# MCU.net
KiCad netlist of a schematic drawn in Altium Designer
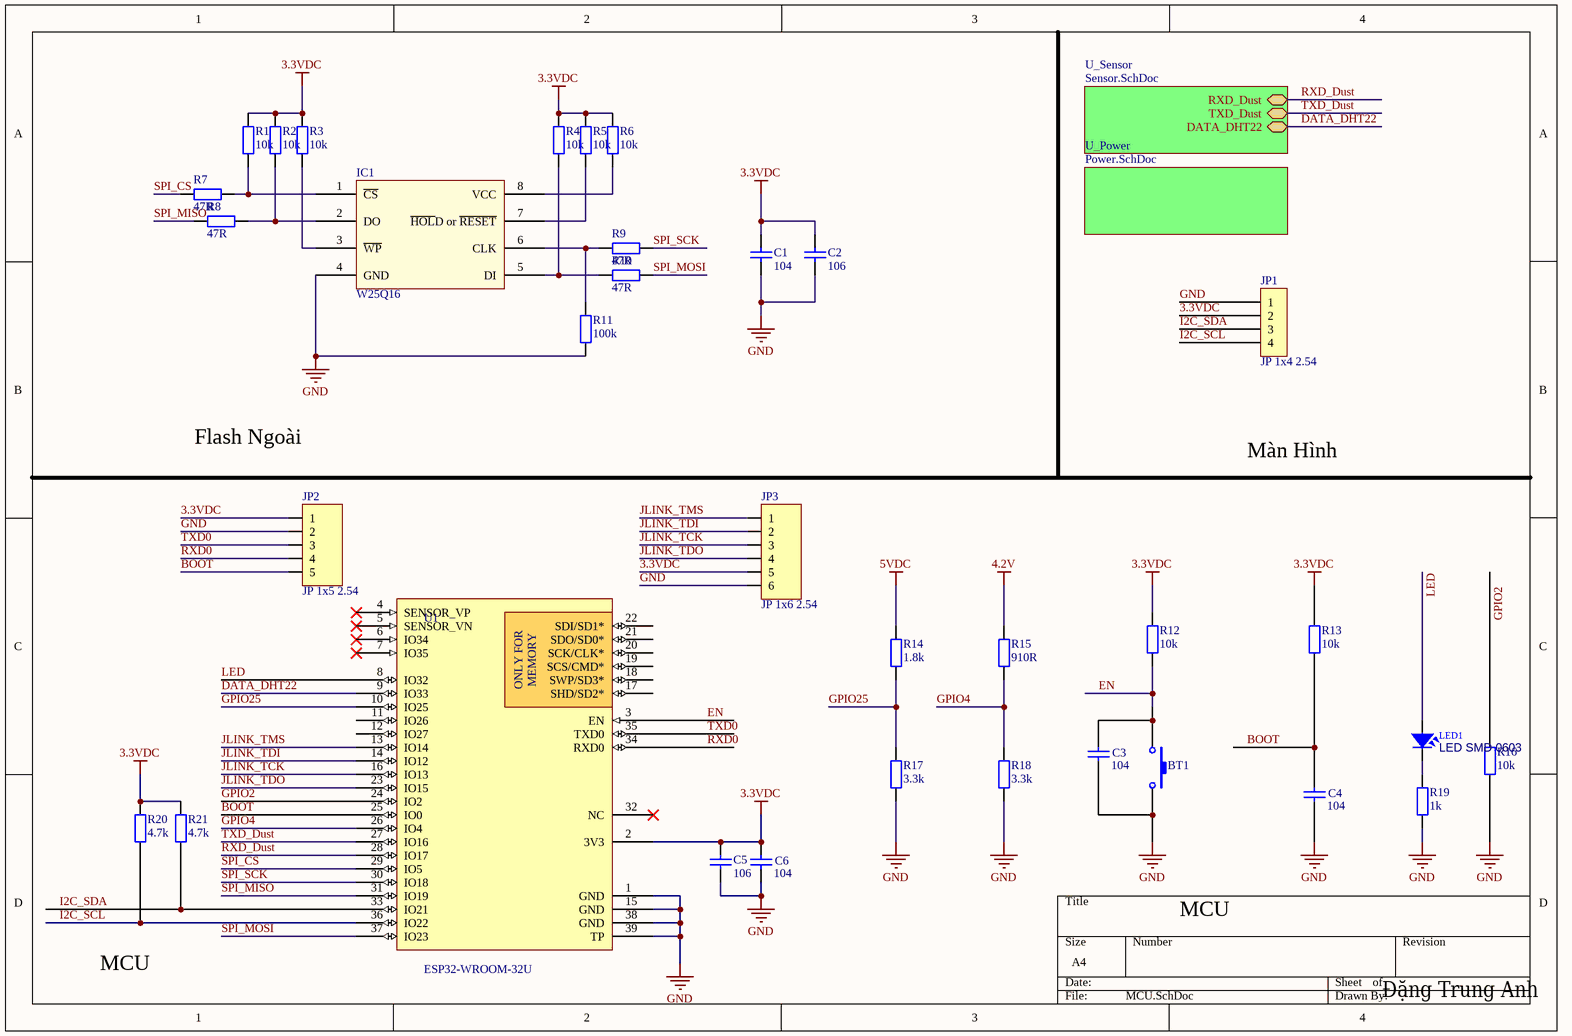
[diagram p0: MCU.SchDoc]

(export (version "E")
  (design (tool "Eeschema 10.0.6"))
  (components
    (comp (ref "BT1")
      (value "Nut Nhan 2 Chan SMD 3x6x2.5")
      (footprint "Nut Nhan 2 Chan SMD 3x6x2.5")
      (libsource (lib "Altium_Lib_by_KhueNguyenCreator") (part "Nut Nhan 2 Chan SMD 3x6x2.5"))
    )
    (comp (ref "C1")
      (value "104")
      (footprint "tu 0603")
      (description "Dán")
      (libsource (lib "Altium_Lib_by_KhueNguyenCreator") (part "Tu 0603 104 50V 10%"))
    )
    (comp (ref "C2")
      (value "106")
      (footprint "tu 0603")
      (description "Dán")
      (libsource (lib "THU VIEN SCH") (part "Tu 0603 106 16V 20%"))
    )
    (comp (ref "C3")
      (value "104")
      (footprint "tu 0603")
      (description "Dán")
      (libsource (lib "Altium_Lib_by_KhueNguyenCreator") (part "Tu 0603 104 50V 10%"))
    )
    (comp (ref "C4")
      (value "104")
      (footprint "tu 0603")
      (description "Dán")
      (libsource (lib "Altium_Lib_by_KhueNguyenCreator") (part "Tu 0603 104 50V 10%"))
    )
    (comp (ref "C5")
      (value "106")
      (footprint "tu 0603")
      (description "Dán")
      (libsource (lib "THU VIEN SCH") (part "Tu 0603 106 16V 20%"))
    )
    (comp (ref "C6")
      (value "104")
      (footprint "tu 0603")
      (description "Dán")
      (libsource (lib "Altium_Lib_by_KhueNguyenCreator") (part "Tu 0603 104 50V 10%"))
    )
    (comp (ref "IC1")
      (value "W25Q16")
      (footprint "W25Q16 -SOIC8")
      (libsource (lib "Integrated_Library") (part "W25Q16"))
    )
    (comp (ref "JP1")
      (value "JP 1x4 2.54")
      (footprint "JP 1x4 DT")
      (description "Cắm")
      (libsource (lib "Altium_Lib_by_KhueNguyenCreator") (part "JP 1x4 2.54 Duc Thang"))
    )
    (comp (ref "JP2")
      (value "JP 1x5 2.54")
      (footprint "JP 1x5 DT")
      (description "Cắm")
      (libsource (lib "Altium_Lib_by_KhueNguyenCreator") (part "JP 1x5 2.54 Duc Thang"))
    )
    (comp (ref "JP3")
      (value "JP 1x6 2.54")
      (footprint "JP 1x6 DT")
      (description "Cắm")
      (libsource (lib "Altium_Lib_by_KhueNguyenCreator") (part "JP 1x6 2.54 Duc Thang"))
    )
    (comp (ref "LED1")
      (value "LED SMD 0603")
      (footprint "LED-0603-BLUE")
      (description "LED 0603 SMD Green 525nm 350mcd 20mA")
      (libsource (lib "My library altium") (part "LED SMD 0603"))
    )
    (comp (ref "R1")
      (value "10k")
      (footprint "tro smd 0603")
      (description "Dán")
      (libsource (lib "THU VIEN SCH") (part "Tro 0603 1% 10k"))
    )
    (comp (ref "R2")
      (value "10k")
      (footprint "tro smd 0603")
      (description "Dán")
      (libsource (lib "THU VIEN SCH") (part "Tro 0603 1% 10k"))
    )
    (comp (ref "R3")
      (value "10k")
      (footprint "tro smd 0603")
      (description "Dán")
      (libsource (lib "THU VIEN SCH") (part "Tro 0603 1% 10k"))
    )
    (comp (ref "R4")
      (value "10k")
      (footprint "tro smd 0603")
      (description "Dán")
      (libsource (lib "THU VIEN SCH") (part "Tro 0603 1% 10k"))
    )
    (comp (ref "R5")
      (value "10k")
      (footprint "tro smd 0603")
      (description "Dán")
      (libsource (lib "THU VIEN SCH") (part "Tro 0603 1% 10k"))
    )
    (comp (ref "R6")
      (value "10k")
      (footprint "tro smd 0603")
      (description "Dán")
      (libsource (lib "THU VIEN SCH") (part "Tro 0603 1% 10k"))
    )
    (comp (ref "R7")
      (value "47R")
      (footprint "tro smd 0603")
      (description "Dán")
      (libsource (lib "Altium_Lib_by_KhueNguyenCreator") (part "Tro 0603 1% 47R"))
    )
    (comp (ref "R8")
      (value "47R")
      (footprint "tro smd 0603")
      (description "Dán")
      (libsource (lib "Altium_Lib_by_KhueNguyenCreator") (part "Tro 0603 1% 47R"))
    )
    (comp (ref "R9")
      (value "47R")
      (footprint "tro smd 0603")
      (description "Dán")
      (libsource (lib "Altium_Lib_by_KhueNguyenCreator") (part "Tro 0603 1% 47R"))
    )
    (comp (ref "R10")
      (value "47R")
      (footprint "tro smd 0603")
      (description "Dán")
      (libsource (lib "Altium_Lib_by_KhueNguyenCreator") (part "Tro 0603 1% 47R"))
    )
    (comp (ref "R11")
      (value "100k")
      (footprint "tro smd 0603")
      (description "Dán")
      (libsource (lib "Altium_Lib_by_KhueNguyenCreator") (part "Tro 0603 5% 100k"))
    )
    (comp (ref "R12")
      (value "10k")
      (footprint "tro smd 0603")
      (description "Dán")
      (libsource (lib "THU VIEN SCH") (part "Tro 0603 1% 10k"))
    )
    (comp (ref "R13")
      (value "10k")
      (footprint "tro smd 0603")
      (description "Dán")
      (libsource (lib "THU VIEN SCH") (part "Tro 0603 1% 10k"))
    )
    (comp (ref "R14")
      (value "1.8k")
      (footprint "tro smd 0603")
      (description "Dán")
      (libsource (lib "Altium_Lib_by_KhueNguyenCreator") (part "Tro 0603 1% 1.8k"))
    )
    (comp (ref "R15")
      (value "910R")
      (footprint "tro smd 0603")
      (description "Dán")
      (libsource (lib "Altium_Lib_by_KhueNguyenCreator") (part "Tro 0603 1% 910R"))
    )
    (comp (ref "R16")
      (value "10k")
      (footprint "tro smd 0603")
      (description "Dán")
      (libsource (lib "THU VIEN SCH") (part "Tro 0603 1% 10k"))
    )
    (comp (ref "R17")
      (value "3.3k")
      (footprint "tro smd 0603")
      (description "Dán")
      (libsource (lib "Altium_Lib_by_KhueNguyenCreator") (part "Tro 0603 5% 3.3k"))
    )
    (comp (ref "R18")
      (value "3.3k")
      (footprint "tro smd 0603")
      (description "Dán")
      (libsource (lib "Altium_Lib_by_KhueNguyenCreator") (part "Tro 0603 5% 3.3k"))
    )
    (comp (ref "R19")
      (value "1k")
      (footprint "tro smd 0603")
      (description "Dán")
      (libsource (lib "Altium_Lib_by_KhueNguyenCreator") (part "Tro 0603 5% 1k"))
    )
    (comp (ref "R20")
      (value "4.7k")
      (footprint "tro smd 0603")
      (description "Dán")
      (libsource (lib "Altium_Lib_by_KhueNguyenCreator") (part "Tro 0603 5% 4.7k"))
    )
    (comp (ref "R21")
      (value "4.7k")
      (footprint "tro smd 0603")
      (description "Dán")
      (libsource (lib "Altium_Lib_by_KhueNguyenCreator") (part "Tro 0603 5% 4.7k"))
    )
    (comp (ref "U1")
      (value "ESP32-WROOM-32U")
      (footprint "ESP32-WROOM-32")
      (description "Wi-Fi/BT BLE Module ESP32-D0WD")
      (fields (field (name "MFR") "Espressif"))
      (libsource (lib "BYTECH_HW_LIB_2019 (1)") (part "ESP32-WROOM-32U"))
    )
  )
  (nets
    (net (code "1") (name "/BOOT") (class "Default")
      (node (ref "C4") (pin "1") (pinfunction "1_1") (pintype "passive"))
      (node (ref "JP2") (pin "5") (pinfunction "5_5") (pintype "passive"))
      (node (ref "R13") (pin "1") (pinfunction "1_1") (pintype "passive"))
      (node (ref "U1") (pin "25") (pinfunction "IO0_25") (pintype "bidirectional"))
    )
    (net (code "2") (name "/DATA_DHT22") (class "Default")
      (node (ref "U1") (pin "9") (pinfunction "IO33_9") (pintype "bidirectional"))
    )
    (net (code "3") (name "/EN") (class "Default")
      (node (ref "BT1") (pin "1") (pinfunction "1_1") (pintype "passive"))
      (node (ref "C3") (pin "1") (pinfunction "1_1") (pintype "passive"))
      (node (ref "R12") (pin "1") (pinfunction "1_1") (pintype "passive"))
      (node (ref "U1") (pin "3") (pinfunction "EN_3") (pintype "input"))
    )
    (net (code "4") (name "/GPIO2") (class "Default")
      (node (ref "R16") (pin "2") (pinfunction "2_2") (pintype "passive"))
      (node (ref "U1") (pin "24") (pinfunction "IO2_24") (pintype "bidirectional"))
    )
    (net (code "5") (name "/GPIO4") (class "Default")
      (node (ref "R15") (pin "1") (pinfunction "1_1") (pintype "passive"))
      (node (ref "R18") (pin "2") (pinfunction "2_2") (pintype "passive"))
      (node (ref "U1") (pin "26") (pinfunction "IO4_26") (pintype "bidirectional"))
    )
    (net (code "6") (name "/GPIO25") (class "Default")
      (node (ref "R14") (pin "1") (pinfunction "1_1") (pintype "passive"))
      (node (ref "R17") (pin "2") (pinfunction "2_2") (pintype "passive"))
      (node (ref "U1") (pin "10") (pinfunction "IO25_10") (pintype "bidirectional"))
    )
    (net (code "7") (name "/I2C_SCL") (class "Default")
      (node (ref "JP1") (pin "4") (pinfunction "4_4") (pintype "passive"))
      (node (ref "R20") (pin "1") (pinfunction "1_1") (pintype "passive"))
      (node (ref "U1") (pin "36") (pinfunction "IO22_36") (pintype "bidirectional"))
    )
    (net (code "8") (name "/I2C_SDA") (class "Default")
      (node (ref "JP1") (pin "3") (pinfunction "3_3") (pintype "passive"))
      (node (ref "R21") (pin "1") (pinfunction "1_1") (pintype "passive"))
      (node (ref "U1") (pin "33") (pinfunction "IO21_33") (pintype "bidirectional"))
    )
    (net (code "9") (name "/JLINK_TCK") (class "Default")
      (node (ref "JP3") (pin "3") (pinfunction "3_3") (pintype "passive"))
      (node (ref "U1") (pin "16") (pinfunction "IO13_16") (pintype "bidirectional"))
    )
    (net (code "10") (name "/JLINK_TDI") (class "Default")
      (node (ref "JP3") (pin "2") (pinfunction "2_2") (pintype "passive"))
      (node (ref "U1") (pin "14") (pinfunction "IO12_14") (pintype "bidirectional"))
    )
    (net (code "11") (name "/JLINK_TDO") (class "Default")
      (node (ref "JP3") (pin "4") (pinfunction "4_4") (pintype "passive"))
      (node (ref "U1") (pin "23") (pinfunction "IO15_23") (pintype "bidirectional"))
    )
    (net (code "12") (name "/JLINK_TMS") (class "Default")
      (node (ref "JP3") (pin "1") (pinfunction "1_1") (pintype "passive"))
      (node (ref "U1") (pin "13") (pinfunction "IO14_13") (pintype "bidirectional"))
    )
    (net (code "13") (name "/LED") (class "Default")
      (node (ref "LED1") (pin "A") (pinfunction "A_A") (pintype "passive"))
      (node (ref "U1") (pin "8") (pinfunction "IO32_8") (pintype "bidirectional"))
    )
    (net (code "14") (name "/RXD0") (class "Default")
      (node (ref "JP2") (pin "4") (pinfunction "4_4") (pintype "passive"))
      (node (ref "U1") (pin "34") (pinfunction "RXD0_34") (pintype "bidirectional"))
    )
    (net (code "15") (name "/RXD_Dust") (class "Default")
      (node (ref "U1") (pin "28") (pinfunction "IO17_28") (pintype "bidirectional"))
    )
    (net (code "16") (name "/SPI_CS") (class "Default")
      (node (ref "R7") (pin "1") (pinfunction "1_1") (pintype "passive"))
      (node (ref "U1") (pin "29") (pinfunction "IO5_29") (pintype "bidirectional"))
    )
    (net (code "17") (name "/SPI_MISO") (class "Default")
      (node (ref "R8") (pin "1") (pinfunction "1_1") (pintype "passive"))
      (node (ref "U1") (pin "31") (pinfunction "IO19_31") (pintype "bidirectional"))
    )
    (net (code "18") (name "/SPI_MOSI") (class "Default")
      (node (ref "R10") (pin "2") (pinfunction "2_2") (pintype "passive"))
      (node (ref "U1") (pin "37") (pinfunction "IO23_37") (pintype "bidirectional"))
    )
    (net (code "19") (name "/SPI_SCK") (class "Default")
      (node (ref "R9") (pin "2") (pinfunction "2_2") (pintype "passive"))
      (node (ref "U1") (pin "30") (pinfunction "IO18_30") (pintype "bidirectional"))
    )
    (net (code "20") (name "/TXD0") (class "Default")
      (node (ref "JP2") (pin "3") (pinfunction "3_3") (pintype "passive"))
      (node (ref "U1") (pin "35") (pinfunction "TXD0_35") (pintype "bidirectional"))
    )
    (net (code "21") (name "/TXD_Dust") (class "Default")
      (node (ref "U1") (pin "27") (pinfunction "IO16_27") (pintype "bidirectional"))
    )
    (net (code "22") (name "3.3VDC") (class "Default")
      (node (ref "C1") (pin "1") (pinfunction "1_1") (pintype "passive"))
      (node (ref "C2") (pin "1") (pinfunction "1_1") (pintype "passive"))
      (node (ref "C5") (pin "1") (pinfunction "1_1") (pintype "passive"))
      (node (ref "C6") (pin "1") (pinfunction "1_1") (pintype "passive"))
      (node (ref "JP1") (pin "2") (pinfunction "2_2") (pintype "passive"))
      (node (ref "JP2") (pin "1") (pinfunction "1_1") (pintype "passive"))
      (node (ref "JP3") (pin "5") (pinfunction "5_5") (pintype "passive"))
      (node (ref "R1") (pin "2") (pinfunction "2_2") (pintype "passive"))
      (node (ref "R12") (pin "2") (pinfunction "2_2") (pintype "passive"))
      (node (ref "R13") (pin "2") (pinfunction "2_2") (pintype "passive"))
      (node (ref "R2") (pin "2") (pinfunction "2_2") (pintype "passive"))
      (node (ref "R20") (pin "2") (pinfunction "2_2") (pintype "passive"))
      (node (ref "R21") (pin "2") (pinfunction "2_2") (pintype "passive"))
      (node (ref "R3") (pin "2") (pinfunction "2_2") (pintype "passive"))
      (node (ref "R4") (pin "2") (pinfunction "2_2") (pintype "passive"))
      (node (ref "R5") (pin "2") (pinfunction "2_2") (pintype "passive"))
      (node (ref "R6") (pin "2") (pinfunction "2_2") (pintype "passive"))
      (node (ref "U1") (pin "2") (pinfunction "3V3_2") (pintype "power_in"))
    )
    (net (code "23") (name "4.2V") (class "Default")
      (node (ref "R15") (pin "2") (pinfunction "2_2") (pintype "passive"))
    )
    (net (code "24") (name "5VDC") (class "Default")
      (node (ref "R14") (pin "2") (pinfunction "2_2") (pintype "passive"))
    )
    (net (code "25") (name "GND") (class "Default")
      (node (ref "BT1") (pin "2") (pinfunction "2_2") (pintype "passive"))
      (node (ref "C1") (pin "2") (pinfunction "2_2") (pintype "passive"))
      (node (ref "C2") (pin "2") (pinfunction "2_2") (pintype "passive"))
      (node (ref "C3") (pin "2") (pinfunction "2_2") (pintype "passive"))
      (node (ref "C4") (pin "2") (pinfunction "2_2") (pintype "passive"))
      (node (ref "C5") (pin "2") (pinfunction "2_2") (pintype "passive"))
      (node (ref "C6") (pin "2") (pinfunction "2_2") (pintype "passive"))
      (node (ref "IC1") (pin "4") (pinfunction "GND_4") (pintype "passive"))
      (node (ref "JP1") (pin "1") (pinfunction "1_1") (pintype "passive"))
      (node (ref "JP2") (pin "2") (pinfunction "2_2") (pintype "passive"))
      (node (ref "JP3") (pin "6") (pinfunction "6_6") (pintype "passive"))
      (node (ref "R11") (pin "1") (pinfunction "1_1") (pintype "passive"))
      (node (ref "R16") (pin "1") (pinfunction "1_1") (pintype "passive"))
      (node (ref "R17") (pin "1") (pinfunction "1_1") (pintype "passive"))
      (node (ref "R18") (pin "1") (pinfunction "1_1") (pintype "passive"))
      (node (ref "R19") (pin "1") (pinfunction "1_1") (pintype "passive"))
      (node (ref "U1") (pin "1") (pinfunction "GND_1") (pintype "power_in"))
      (node (ref "U1") (pin "15") (pinfunction "GND_15") (pintype "power_in"))
      (node (ref "U1") (pin "38") (pinfunction "GND_38") (pintype "power_in"))
      (node (ref "U1") (pin "39") (pinfunction "TP_39") (pintype "power_in"))
    )
    (net (code "26") (name "Net-(IC1-CLK)") (class "Default")
      (node (ref "IC1") (pin "6") (pinfunction "CLK_6") (pintype "passive"))
      (node (ref "R11") (pin "2") (pinfunction "2_2") (pintype "passive"))
      (node (ref "R9") (pin "1") (pinfunction "1_1") (pintype "passive"))
    )
    (net (code "27") (name "Net-(IC1-DI)") (class "Default")
      (node (ref "IC1") (pin "5") (pinfunction "DI_5") (pintype "passive"))
      (node (ref "R10") (pin "1") (pinfunction "1_1") (pintype "passive"))
      (node (ref "R4") (pin "1") (pinfunction "1_1") (pintype "passive"))
    )
    (net (code "28") (name "Net-(IC1-DO)") (class "Default")
      (node (ref "IC1") (pin "2") (pinfunction "DO_2") (pintype "passive"))
      (node (ref "R2") (pin "1") (pinfunction "1_1") (pintype "passive"))
      (node (ref "R8") (pin "2") (pinfunction "2_2") (pintype "passive"))
    )
    (net (code "29") (name "Net-(IC1-VCC)") (class "Default")
      (node (ref "IC1") (pin "8") (pinfunction "VCC_8") (pintype "passive"))
      (node (ref "R6") (pin "1") (pinfunction "1_1") (pintype "passive"))
    )
    (net (code "30") (name "Net-(IC1-~{CS})") (class "Default")
      (node (ref "IC1") (pin "1") (pinfunction "~{CS}_1") (pintype "passive"))
      (node (ref "R1") (pin "1") (pinfunction "1_1") (pintype "passive"))
      (node (ref "R7") (pin "2") (pinfunction "2_2") (pintype "passive"))
    )
    (net (code "31") (name "Net-(IC1-~{HOL}D_or_~{RESET})") (class "Default")
      (node (ref "IC1") (pin "7") (pinfunction "~{HOL}D_or_~{RESET}_7") (pintype "passive"))
      (node (ref "R5") (pin "1") (pinfunction "1_1") (pintype "passive"))
    )
    (net (code "32") (name "Net-(IC1-~{WP})") (class "Default")
      (node (ref "IC1") (pin "3") (pinfunction "~{WP}_3") (pintype "passive"))
      (node (ref "R3") (pin "1") (pinfunction "1_1") (pintype "passive"))
    )
    (net (code "33") (name "Net-(LED1-PadK)") (class "Default")
      (node (ref "LED1") (pin "K") (pinfunction "K_K") (pintype "passive"))
      (node (ref "R19") (pin "2") (pinfunction "2_2") (pintype "passive"))
    )
    (net (code "34") (name "unconnected-(U1-IO26-Pad11)") (class "Default")
      (node (ref "U1") (pin "11") (pinfunction "IO26_11") (pintype "bidirectional"))
    )
    (net (code "35") (name "unconnected-(U1-IO27-Pad12)") (class "Default")
      (node (ref "U1") (pin "12") (pinfunction "IO27_12") (pintype "bidirectional"))
    )
    (net (code "36") (name "unconnected-(U1-IO34-Pad6)") (class "Default")
      (node (ref "U1") (pin "6") (pinfunction "IO34_6") (pintype "input+no_connect"))
    )
    (net (code "37") (name "unconnected-(U1-IO35-Pad7)") (class "Default")
      (node (ref "U1") (pin "7") (pinfunction "IO35_7") (pintype "input+no_connect"))
    )
    (net (code "38") (name "unconnected-(U1-NC-Pad32)") (class "Default")
      (node (ref "U1") (pin "32") (pinfunction "NC_32") (pintype "passive+no_connect"))
    )
    (net (code "39") (name "unconnected-(U1-SCK{slash}CLK*-Pad20)") (class "Default")
      (node (ref "U1") (pin "20") (pinfunction "SCK/CLK*_20") (pintype "bidirectional"))
    )
    (net (code "40") (name "unconnected-(U1-SCS{slash}CMD*-Pad19)") (class "Default")
      (node (ref "U1") (pin "19") (pinfunction "SCS/CMD*_19") (pintype "bidirectional"))
    )
    (net (code "41") (name "unconnected-(U1-SDI{slash}SD1*-Pad22)") (class "Default")
      (node (ref "U1") (pin "22") (pinfunction "SDI/SD1*_22") (pintype "bidirectional"))
    )
    (net (code "42") (name "unconnected-(U1-SDO{slash}SD0*-Pad21)") (class "Default")
      (node (ref "U1") (pin "21") (pinfunction "SDO/SD0*_21") (pintype "bidirectional"))
    )
    (net (code "43") (name "unconnected-(U1-SENSOR_VN-Pad5)") (class "Default")
      (node (ref "U1") (pin "5") (pinfunction "SENSOR_VN_5") (pintype "input+no_connect"))
    )
    (net (code "44") (name "unconnected-(U1-SENSOR_VP-Pad4)") (class "Default")
      (node (ref "U1") (pin "4") (pinfunction "SENSOR_VP_4") (pintype "input+no_connect"))
    )
    (net (code "45") (name "unconnected-(U1-SHD{slash}SD2*-Pad17)") (class "Default")
      (node (ref "U1") (pin "17") (pinfunction "SHD/SD2*_17") (pintype "bidirectional"))
    )
    (net (code "46") (name "unconnected-(U1-SWP{slash}SD3*-Pad18)") (class "Default")
      (node (ref "U1") (pin "18") (pinfunction "SWP/SD3*_18") (pintype "bidirectional"))
    )
  )
)
